# uNimbus_board_1_v1_2.net
KiCad netlist of a schematic drawn in EAGLE
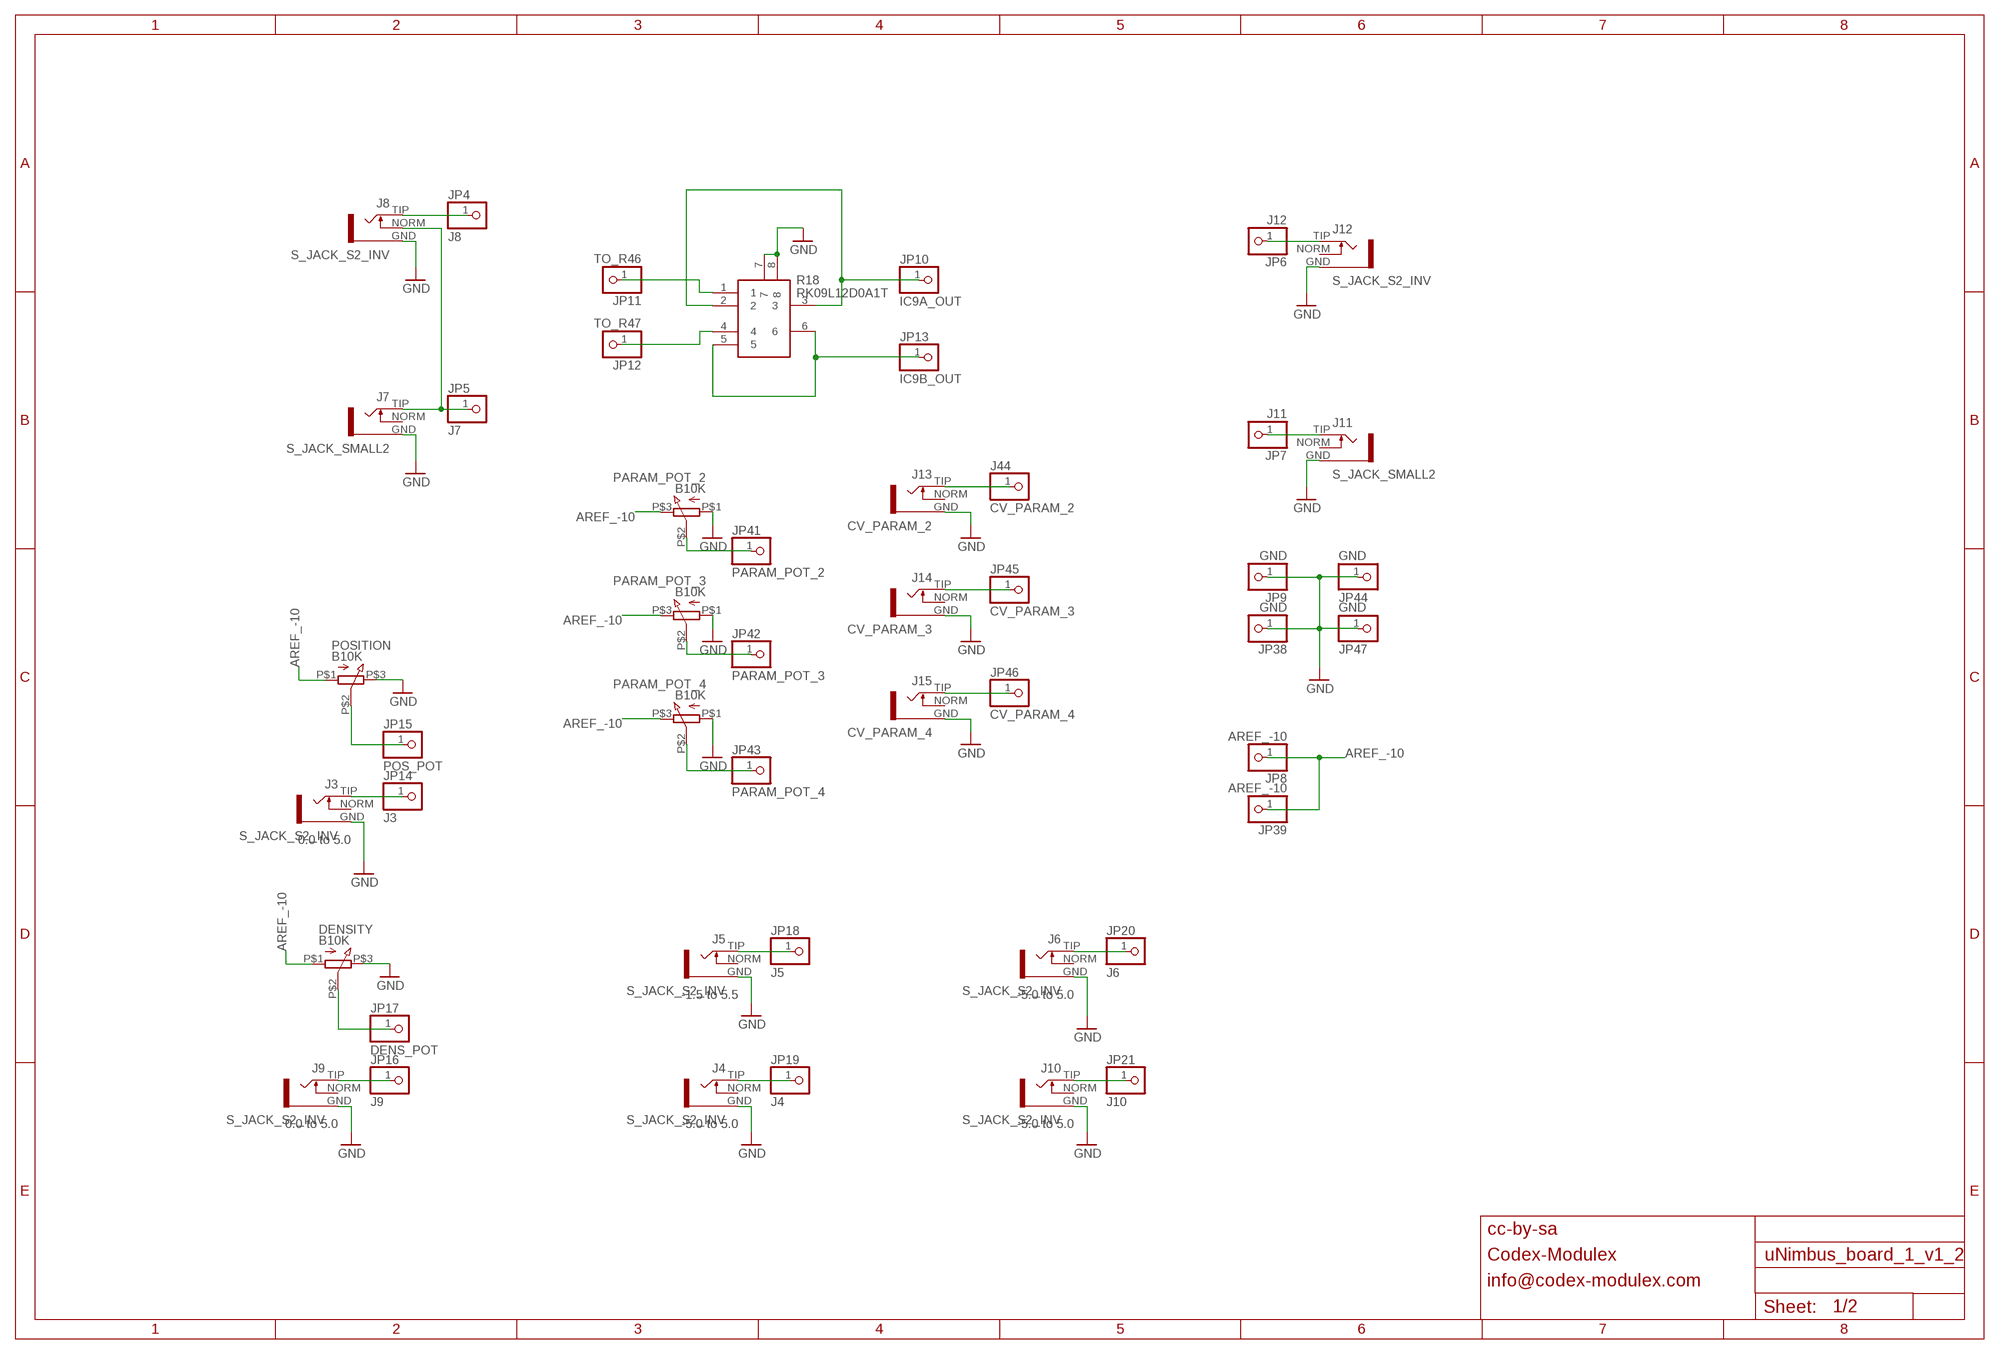
[diagram p0: schematic, sheet 1]
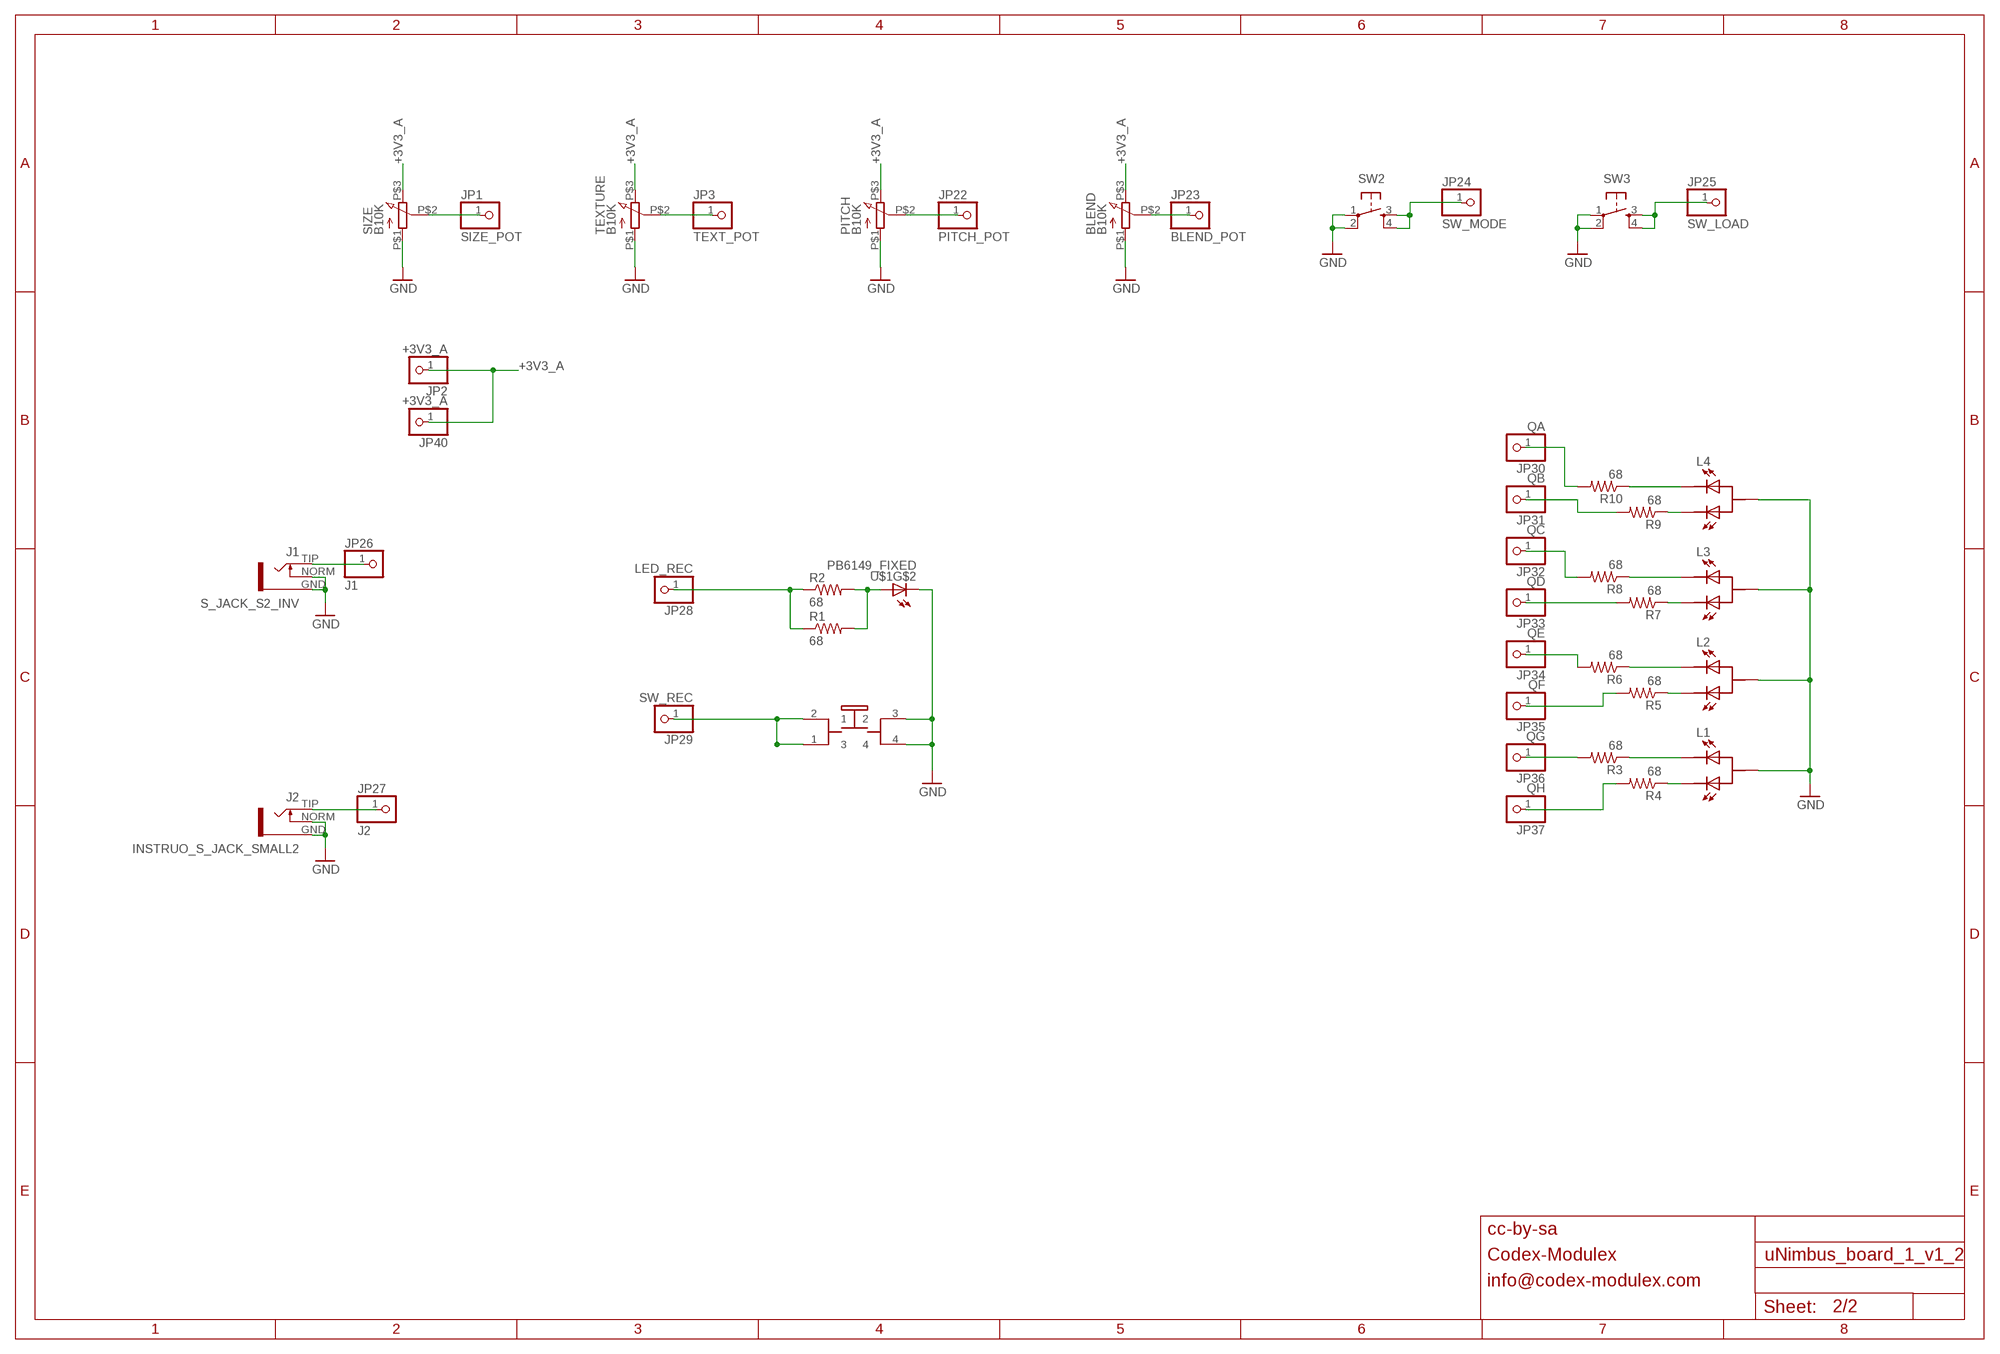
[diagram p1: schematic, sheet 2]

(export (version "E")
  (design (tool "Eeschema 10.0.6"))
  (components
    (comp (ref "BLEND")
      (value "B10K")
      (footprint "eagle-import:Q-POT2")
      (libsource (lib "eagle-import") (part "Q-POT2"))
    )
    (comp (ref "J1")
      (value "S_JACK_S2_INV")
      (footprint "eagle-import:S_JACK_S2_INV")
      (libsource (lib "eagle-import") (part "S_JACK_S2_INV"))
    )
    (comp (ref "J2")
      (value "INSTRUO_S_JACK_SMALL2")
      (footprint "eagle-import:INSTRUO_S_JACK_SMALL2")
      (libsource (lib "eagle-import") (part "INSTRUO_S_JACK_SMALL2"))
    )
    (comp (ref "JP1")
      (value "SIZE_POT")
      (footprint "eagle-import:PARTS_AMAN_1X01")
      (libsource (lib "eagle-import") (part "PARTS_AMAN_PINHD-1X1"))
    )
    (comp (ref "JP2")
      (value "+3V3_A")
      (footprint "eagle-import:PARTS_AMAN_1X01")
      (libsource (lib "eagle-import") (part "PARTS_AMAN_PINHD-1X1"))
    )
    (comp (ref "JP3")
      (value "TEXT_POT")
      (footprint "eagle-import:PARTS_AMAN_1X01")
      (libsource (lib "eagle-import") (part "PARTS_AMAN_PINHD-1X1"))
    )
    (comp (ref "JP22")
      (value "PITCH_POT")
      (footprint "eagle-import:PARTS_AMAN_1X01")
      (libsource (lib "eagle-import") (part "PARTS_AMAN_PINHD-1X1"))
    )
    (comp (ref "JP23")
      (value "BLEND_POT")
      (footprint "eagle-import:PARTS_AMAN_1X01")
      (libsource (lib "eagle-import") (part "PARTS_AMAN_PINHD-1X1"))
    )
    (comp (ref "JP24")
      (value "SW_MODE")
      (footprint "eagle-import:PARTS_AMAN_1X01")
      (libsource (lib "eagle-import") (part "PARTS_AMAN_PINHD-1X1"))
    )
    (comp (ref "JP25")
      (value "SW_LOAD")
      (footprint "eagle-import:PARTS_AMAN_1X01")
      (libsource (lib "eagle-import") (part "PARTS_AMAN_PINHD-1X1"))
    )
    (comp (ref "JP26")
      (value "J1")
      (footprint "eagle-import:PARTS_AMAN_1X01")
      (libsource (lib "eagle-import") (part "PARTS_AMAN_PINHD-1X1"))
    )
    (comp (ref "JP27")
      (value "J2")
      (footprint "eagle-import:PARTS_AMAN_1X01")
      (libsource (lib "eagle-import") (part "PARTS_AMAN_PINHD-1X1"))
    )
    (comp (ref "JP28")
      (value "LED_REC")
      (footprint "eagle-import:PARTS_AMAN_1X01")
      (libsource (lib "eagle-import") (part "PARTS_AMAN_PINHD-1X1"))
    )
    (comp (ref "JP29")
      (value "SW_REC")
      (footprint "eagle-import:PARTS_AMAN_1X01")
      (libsource (lib "eagle-import") (part "PARTS_AMAN_PINHD-1X1"))
    )
    (comp (ref "JP30")
      (value "QA")
      (footprint "eagle-import:PARTS_AMAN_1X01")
      (libsource (lib "eagle-import") (part "PARTS_AMAN_PINHD-1X1"))
    )
    (comp (ref "JP31")
      (value "QB")
      (footprint "eagle-import:PARTS_AMAN_1X01")
      (libsource (lib "eagle-import") (part "PARTS_AMAN_PINHD-1X1"))
    )
    (comp (ref "JP32")
      (value "QC")
      (footprint "eagle-import:PARTS_AMAN_1X01")
      (libsource (lib "eagle-import") (part "PARTS_AMAN_PINHD-1X1"))
    )
    (comp (ref "JP33")
      (value "QD")
      (footprint "eagle-import:PARTS_AMAN_1X01")
      (libsource (lib "eagle-import") (part "PARTS_AMAN_PINHD-1X1"))
    )
    (comp (ref "JP34")
      (value "QE")
      (footprint "eagle-import:PARTS_AMAN_1X01")
      (libsource (lib "eagle-import") (part "PARTS_AMAN_PINHD-1X1"))
    )
    (comp (ref "JP35")
      (value "QF")
      (footprint "eagle-import:PARTS_AMAN_1X01")
      (libsource (lib "eagle-import") (part "PARTS_AMAN_PINHD-1X1"))
    )
    (comp (ref "JP36")
      (value "QG")
      (footprint "eagle-import:PARTS_AMAN_1X01")
      (libsource (lib "eagle-import") (part "PARTS_AMAN_PINHD-1X1"))
    )
    (comp (ref "JP37")
      (value "QH")
      (footprint "eagle-import:PARTS_AMAN_1X01")
      (libsource (lib "eagle-import") (part "PARTS_AMAN_PINHD-1X1"))
    )
    (comp (ref "JP40")
      (value "+3V3_A")
      (footprint "eagle-import:PARTS_AMAN_1X01")
      (libsource (lib "eagle-import") (part "PARTS_AMAN_PINHD-1X1"))
    )
    (comp (ref "L1")
      (value "LED_3MM_3PIN")
      (footprint "eagle-import:LED_3MM_3PIN")
      (libsource (lib "eagle-import") (part "LED_3MM_3PIN"))
    )
    (comp (ref "L2")
      (value "LED_3MM_3PIN")
      (footprint "eagle-import:LED_3MM_3PIN")
      (libsource (lib "eagle-import") (part "LED_3MM_3PIN"))
    )
    (comp (ref "L3")
      (value "LED_3MM_3PIN")
      (footprint "eagle-import:LED_3MM_3PIN")
      (libsource (lib "eagle-import") (part "LED_3MM_3PIN"))
    )
    (comp (ref "L4")
      (value "LED_3MM_3PIN")
      (footprint "eagle-import:LED_3MM_3PIN")
      (libsource (lib "eagle-import") (part "LED_3MM_3PIN"))
    )
    (comp (ref "PITCH")
      (value "B10K")
      (footprint "eagle-import:Q-POT2")
      (libsource (lib "eagle-import") (part "Q-POT2"))
    )
    (comp (ref "R1")
      (value "68")
      (footprint "eagle-import:R0603")
      (libsource (lib "eagle-import") (part "R-US_R0603"))
    )
    (comp (ref "R2")
      (value "68")
      (footprint "eagle-import:R0603")
      (libsource (lib "eagle-import") (part "R-US_R0603"))
    )
    (comp (ref "R3")
      (value "68")
      (footprint "eagle-import:R0603")
      (libsource (lib "eagle-import") (part "R-US_R0603"))
    )
    (comp (ref "R4")
      (value "68")
      (footprint "eagle-import:R0603")
      (libsource (lib "eagle-import") (part "R-US_R0603"))
    )
    (comp (ref "R5")
      (value "68")
      (footprint "eagle-import:R0603")
      (libsource (lib "eagle-import") (part "R-US_R0603"))
    )
    (comp (ref "R6")
      (value "68")
      (footprint "eagle-import:R0603")
      (libsource (lib "eagle-import") (part "R-US_R0603"))
    )
    (comp (ref "R7")
      (value "68")
      (footprint "eagle-import:R0603")
      (libsource (lib "eagle-import") (part "R-US_R0603"))
    )
    (comp (ref "R8")
      (value "68")
      (footprint "eagle-import:R0603")
      (libsource (lib "eagle-import") (part "R-US_R0603"))
    )
    (comp (ref "R9")
      (value "68")
      (footprint "eagle-import:R0603")
      (libsource (lib "eagle-import") (part "R-US_R0603"))
    )
    (comp (ref "R10")
      (value "68")
      (footprint "eagle-import:R0603")
      (libsource (lib "eagle-import") (part "R-US_R0603"))
    )
    (comp (ref "SIZE")
      (value "B10K")
      (footprint "eagle-import:Q-POT2")
      (libsource (lib "eagle-import") (part "Q-POT2"))
    )
    (comp (ref "SW2")
      (value "TAC_SWITCHPTH")
      (footprint "eagle-import:TACTILE-PTH")
      (libsource (lib "eagle-import") (part "TAC_SWITCHPTH"))
    )
    (comp (ref "SW3")
      (value "TAC_SWITCHPTH")
      (footprint "eagle-import:TACTILE-PTH")
      (libsource (lib "eagle-import") (part "TAC_SWITCHPTH"))
    )
    (comp (ref "TEXTURE")
      (value "B10K")
      (footprint "eagle-import:Q-POT2")
      (libsource (lib "eagle-import") (part "Q-POT2"))
    )
    (comp (ref "U$1")
      (value "PB6149_FIXED")
      (footprint "eagle-import:PB6149L")
      (libsource (lib "eagle-import") (part "PB6149_FIXED"))
    )
    (comp (ref "DENSITY")
      (value "B10K")
      (footprint "eagle-import:Q-POT2")
      (libsource (lib "eagle-import") (part "Q-POT2"))
    )
    (comp (ref "J3")
      (value "S_JACK_S2_INV")
      (footprint "eagle-import:S_JACK_S2_INV")
      (libsource (lib "eagle-import") (part "uClouds_002_S_JACK_S2_INV"))
    )
    (comp (ref "J4")
      (value "S_JACK_S2_INV")
      (footprint "eagle-import:S_JACK_S2_INV")
      (libsource (lib "eagle-import") (part "S_JACK_S2_INV"))
    )
    (comp (ref "J5")
      (value "S_JACK_S2_INV")
      (footprint "eagle-import:S_JACK_S2_INV")
      (libsource (lib "eagle-import") (part "S_JACK_S2_INV"))
    )
    (comp (ref "J6")
      (value "S_JACK_S2_INV")
      (footprint "eagle-import:S_JACK_S2_INV")
      (libsource (lib "eagle-import") (part "S_JACK_S2_INV"))
    )
    (comp (ref "J7")
      (value "S_JACK_SMALL2")
      (footprint "eagle-import:S_JACK_SMALL2")
      (libsource (lib "eagle-import") (part "INSTRUO_S_JACK_SMALL2"))
    )
    (comp (ref "J8")
      (value "S_JACK_S2_INV")
      (footprint "eagle-import:S_JACK_S2_INV")
      (libsource (lib "eagle-import") (part "S_JACK_S2_INV"))
    )
    (comp (ref "J9")
      (value "S_JACK_S2_INV")
      (footprint "eagle-import:S_JACK_S2_INV")
      (libsource (lib "eagle-import") (part "S_JACK_S2_INV"))
    )
    (comp (ref "J10")
      (value "S_JACK_S2_INV")
      (footprint "eagle-import:S_JACK_S2_INV")
      (libsource (lib "eagle-import") (part "S_JACK_S2_INV"))
    )
    (comp (ref "J11")
      (value "S_JACK_SMALL2")
      (footprint "eagle-import:S_JACK_SMALL2")
      (libsource (lib "eagle-import") (part "uClouds_002_S_JACK_SMALL2"))
    )
    (comp (ref "J12")
      (value "S_JACK_S2_INV")
      (footprint "eagle-import:S_JACK_S2_INV")
      (libsource (lib "eagle-import") (part "S_JACK_S2_INV"))
    )
    (comp (ref "J13")
      (value "CV_PARAM_2")
      (footprint "eagle-import:S_JACK_S2_INV")
      (libsource (lib "eagle-import") (part "S_JACK_S2_INV"))
    )
    (comp (ref "J14")
      (value "CV_PARAM_3")
      (footprint "eagle-import:S_JACK_S2_INV")
      (libsource (lib "eagle-import") (part "S_JACK_S2_INV"))
    )
    (comp (ref "J15")
      (value "CV_PARAM_4")
      (footprint "eagle-import:S_JACK_S2_INV")
      (libsource (lib "eagle-import") (part "S_JACK_S2_INV"))
    )
    (comp (ref "J44")
      (value "CV_PARAM_2")
      (footprint "eagle-import:PARTS_AMAN_1X01")
      (libsource (lib "eagle-import") (part "PARTS_AMAN_PINHD-1X1"))
    )
    (comp (ref "JP4")
      (value "J8")
      (footprint "eagle-import:PARTS_AMAN_1X01")
      (libsource (lib "eagle-import") (part "PARTS_AMAN_PINHD-1X1"))
    )
    (comp (ref "JP5")
      (value "J7")
      (footprint "eagle-import:PARTS_AMAN_1X01")
      (libsource (lib "eagle-import") (part "PARTS_AMAN_PINHD-1X1"))
    )
    (comp (ref "JP6")
      (value "J12")
      (footprint "eagle-import:PARTS_AMAN_1X01")
      (libsource (lib "eagle-import") (part "PARTS_AMAN_PINHD-1X1"))
    )
    (comp (ref "JP7")
      (value "J11")
      (footprint "eagle-import:PARTS_AMAN_1X01")
      (libsource (lib "eagle-import") (part "PARTS_AMAN_PINHD-1X1"))
    )
    (comp (ref "JP8")
      (value "AREF_-10")
      (footprint "eagle-import:PARTS_AMAN_1X01")
      (libsource (lib "eagle-import") (part "PARTS_AMAN_PINHD-1X1"))
    )
    (comp (ref "JP9")
      (value "GND")
      (footprint "eagle-import:PARTS_AMAN_1X01")
      (libsource (lib "eagle-import") (part "PARTS_AMAN_PINHD-1X1"))
    )
    (comp (ref "JP10")
      (value "IC9A_OUT")
      (footprint "eagle-import:PARTS_AMAN_1X01")
      (libsource (lib "eagle-import") (part "PARTS_AMAN_PINHD-1X1"))
    )
    (comp (ref "JP11")
      (value "TO_R46")
      (footprint "eagle-import:PARTS_AMAN_1X01")
      (libsource (lib "eagle-import") (part "PARTS_AMAN_PINHD-1X1"))
    )
    (comp (ref "JP12")
      (value "TO_R47")
      (footprint "eagle-import:PARTS_AMAN_1X01")
      (libsource (lib "eagle-import") (part "PARTS_AMAN_PINHD-1X1"))
    )
    (comp (ref "JP13")
      (value "IC9B_OUT")
      (footprint "eagle-import:PARTS_AMAN_1X01")
      (libsource (lib "eagle-import") (part "PARTS_AMAN_PINHD-1X1"))
    )
    (comp (ref "JP14")
      (value "J3")
      (footprint "eagle-import:PARTS_AMAN_1X01")
      (libsource (lib "eagle-import") (part "PARTS_AMAN_PINHD-1X1"))
    )
    (comp (ref "JP15")
      (value "POS_POT")
      (footprint "eagle-import:PARTS_AMAN_1X01")
      (libsource (lib "eagle-import") (part "PARTS_AMAN_PINHD-1X1"))
    )
    (comp (ref "JP16")
      (value "J9")
      (footprint "eagle-import:PARTS_AMAN_1X01")
      (libsource (lib "eagle-import") (part "PARTS_AMAN_PINHD-1X1"))
    )
    (comp (ref "JP17")
      (value "DENS_POT")
      (footprint "eagle-import:PARTS_AMAN_1X01")
      (libsource (lib "eagle-import") (part "PARTS_AMAN_PINHD-1X1"))
    )
    (comp (ref "JP18")
      (value "J5")
      (footprint "eagle-import:PARTS_AMAN_1X01")
      (libsource (lib "eagle-import") (part "PARTS_AMAN_PINHD-1X1"))
    )
    (comp (ref "JP19")
      (value "J4")
      (footprint "eagle-import:PARTS_AMAN_1X01")
      (libsource (lib "eagle-import") (part "PARTS_AMAN_PINHD-1X1"))
    )
    (comp (ref "JP20")
      (value "J6")
      (footprint "eagle-import:PARTS_AMAN_1X01")
      (libsource (lib "eagle-import") (part "PARTS_AMAN_PINHD-1X1"))
    )
    (comp (ref "JP21")
      (value "J10")
      (footprint "eagle-import:PARTS_AMAN_1X01")
      (libsource (lib "eagle-import") (part "PARTS_AMAN_PINHD-1X1"))
    )
    (comp (ref "JP38")
      (value "GND")
      (footprint "eagle-import:PARTS_AMAN_1X01")
      (libsource (lib "eagle-import") (part "PARTS_AMAN_PINHD-1X1"))
    )
    (comp (ref "JP39")
      (value "AREF_-10")
      (footprint "eagle-import:PARTS_AMAN_1X01")
      (libsource (lib "eagle-import") (part "PARTS_AMAN_PINHD-1X1"))
    )
    (comp (ref "JP41")
      (value "PARAM_POT_2")
      (footprint "eagle-import:PARTS_AMAN_1X01")
      (libsource (lib "eagle-import") (part "PARTS_AMAN_PINHD-1X1"))
    )
    (comp (ref "JP42")
      (value "PARAM_POT_3")
      (footprint "eagle-import:PARTS_AMAN_1X01")
      (libsource (lib "eagle-import") (part "PARTS_AMAN_PINHD-1X1"))
    )
    (comp (ref "JP43")
      (value "PARAM_POT_4")
      (footprint "eagle-import:PARTS_AMAN_1X01")
      (libsource (lib "eagle-import") (part "PARTS_AMAN_PINHD-1X1"))
    )
    (comp (ref "JP44")
      (value "GND")
      (footprint "eagle-import:PARTS_AMAN_1X01")
      (libsource (lib "eagle-import") (part "PARTS_AMAN_PINHD-1X1"))
    )
    (comp (ref "JP45")
      (value "CV_PARAM_3")
      (footprint "eagle-import:PARTS_AMAN_1X01")
      (libsource (lib "eagle-import") (part "PARTS_AMAN_PINHD-1X1"))
    )
    (comp (ref "JP46")
      (value "CV_PARAM_4")
      (footprint "eagle-import:PARTS_AMAN_1X01")
      (libsource (lib "eagle-import") (part "PARTS_AMAN_PINHD-1X1"))
    )
    (comp (ref "JP47")
      (value "GND")
      (footprint "eagle-import:PARTS_AMAN_1X01")
      (libsource (lib "eagle-import") (part "PARTS_AMAN_PINHD-1X1"))
    )
    (comp (ref "PARAM_POT_2")
      (value "B10K")
      (footprint "eagle-import:Q-POT2")
      (libsource (lib "eagle-import") (part "uClouds_002_Q-POT2"))
    )
    (comp (ref "PARAM_POT_3")
      (value "B10K")
      (footprint "eagle-import:Q-POT2")
      (libsource (lib "eagle-import") (part "uClouds_002_Q-POT2"))
    )
    (comp (ref "PARAM_POT_4")
      (value "B10K")
      (footprint "eagle-import:Q-POT2")
      (libsource (lib "eagle-import") (part "uClouds_002_Q-POT2"))
    )
    (comp (ref "POSITION")
      (value "B10K")
      (footprint "eagle-import:Q-POT2")
      (libsource (lib "eagle-import") (part "Q-POT2"))
    )
    (comp (ref "R18")
      (value "RK09L12D0A1T")
      (footprint "eagle-import:RK09L12D0A1T")
      (fields (field (name "MOUSER_PART_NUMBER") "688-RK09L12D0A1T"))
      (libsource (lib "eagle-import") (part "RK09L12D0A1T"))
    )
  )
  (nets
    (net (code "1") (name "+3V3_A") (class "Default")
      (node (ref "BLEND") (pin "P$3") (pinfunction "3_P$3") (pintype "passive"))
      (node (ref "JP2") (pin "1") (pinfunction "1_1") (pintype "passive"))
      (node (ref "JP40") (pin "1") (pinfunction "1_1") (pintype "passive"))
      (node (ref "PITCH") (pin "P$3") (pinfunction "3_P$3") (pintype "passive"))
      (node (ref "SIZE") (pin "P$3") (pinfunction "3_P$3") (pintype "passive"))
      (node (ref "TEXTURE") (pin "P$3") (pinfunction "3_P$3") (pintype "passive"))
    )
    (net (code "2") (name "AREF_-10") (class "Default")
      (node (ref "DENSITY") (pin "P$1") (pinfunction "1_P$1") (pintype "passive"))
      (node (ref "JP39") (pin "1") (pinfunction "1_1") (pintype "passive"))
      (node (ref "JP8") (pin "1") (pinfunction "1_1") (pintype "passive"))
      (node (ref "PARAM_POT_2") (pin "P$3") (pinfunction "3_P$3") (pintype "passive"))
      (node (ref "PARAM_POT_3") (pin "P$3") (pinfunction "3_P$3") (pintype "passive"))
      (node (ref "PARAM_POT_4") (pin "P$3") (pinfunction "3_P$3") (pintype "passive"))
      (node (ref "POSITION") (pin "P$1") (pinfunction "1_P$1") (pintype "passive"))
    )
    (net (code "3") (name "GND") (class "Default")
      (node (ref "BLEND") (pin "P$1") (pinfunction "1_P$1") (pintype "passive"))
      (node (ref "DENSITY") (pin "P$3") (pinfunction "3_P$3") (pintype "passive"))
      (node (ref "J1") (pin "GND") (pinfunction "GND_GND") (pintype "passive"))
      (node (ref "J1") (pin "NORM") (pinfunction "NORM_NORM") (pintype "passive"))
      (node (ref "J10") (pin "GND") (pinfunction "GND_GND") (pintype "passive"))
      (node (ref "J11") (pin "GND") (pinfunction "GND_GND") (pintype "passive"))
      (node (ref "J12") (pin "GND") (pinfunction "GND_GND") (pintype "passive"))
      (node (ref "J13") (pin "GND") (pinfunction "GND_GND") (pintype "passive"))
      (node (ref "J14") (pin "GND") (pinfunction "GND_GND") (pintype "passive"))
      (node (ref "J15") (pin "GND") (pinfunction "GND_GND") (pintype "passive"))
      (node (ref "J2") (pin "GND") (pinfunction "GND_GND") (pintype "passive"))
      (node (ref "J2") (pin "NORM") (pinfunction "NORM_NORM") (pintype "passive"))
      (node (ref "J3") (pin "GND") (pinfunction "GND_GND") (pintype "passive"))
      (node (ref "J4") (pin "GND") (pinfunction "GND_GND") (pintype "passive"))
      (node (ref "J5") (pin "GND") (pinfunction "GND_GND") (pintype "passive"))
      (node (ref "J6") (pin "GND") (pinfunction "GND_GND") (pintype "passive"))
      (node (ref "J7") (pin "GND") (pinfunction "GND_GND") (pintype "passive"))
      (node (ref "J8") (pin "GND") (pinfunction "GND_GND") (pintype "passive"))
      (node (ref "J9") (pin "GND") (pinfunction "GND_GND") (pintype "passive"))
      (node (ref "JP38") (pin "1") (pinfunction "1_1") (pintype "passive"))
      (node (ref "JP44") (pin "1") (pinfunction "1_1") (pintype "passive"))
      (node (ref "JP47") (pin "1") (pinfunction "1_1") (pintype "passive"))
      (node (ref "JP9") (pin "1") (pinfunction "1_1") (pintype "passive"))
      (node (ref "L1") (pin "A") (pinfunction "A_A") (pintype "passive"))
      (node (ref "L2") (pin "A") (pinfunction "A_A") (pintype "passive"))
      (node (ref "L3") (pin "A") (pinfunction "A_A") (pintype "passive"))
      (node (ref "L4") (pin "A") (pinfunction "A_A") (pintype "passive"))
      (node (ref "PARAM_POT_2") (pin "P$1") (pinfunction "1_P$1") (pintype "passive"))
      (node (ref "PARAM_POT_3") (pin "P$1") (pinfunction "1_P$1") (pintype "passive"))
      (node (ref "PARAM_POT_4") (pin "P$1") (pinfunction "1_P$1") (pintype "passive"))
      (node (ref "PITCH") (pin "P$1") (pinfunction "1_P$1") (pintype "passive"))
      (node (ref "POSITION") (pin "P$3") (pinfunction "3_P$3") (pintype "passive"))
      (node (ref "R18") (pin "7") (pinfunction "7_7") (pintype "bidirectional"))
      (node (ref "R18") (pin "8") (pinfunction "8_8") (pintype "bidirectional"))
      (node (ref "SIZE") (pin "P$1") (pinfunction "1_P$1") (pintype "passive"))
      (node (ref "SW2") (pin "1") (pinfunction "1_1") (pintype "passive"))
      (node (ref "SW2") (pin "2") (pinfunction "2_2") (pintype "passive"))
      (node (ref "SW3") (pin "1") (pinfunction "1_1") (pintype "passive"))
      (node (ref "SW3") (pin "2") (pinfunction "2_2") (pintype "passive"))
      (node (ref "TEXTURE") (pin "P$1") (pinfunction "1_P$1") (pintype "passive"))
      (node (ref "U$1") (pin "3") (pinfunction "2_3") (pintype "bidirectional"))
      (node (ref "U$1") (pin "4") (pinfunction "4_4") (pintype "bidirectional"))
      (node (ref "U$1") (pin "K") (pinfunction "C_K") (pintype "passive"))
    )
    (net (code "4") (name "Net-(BLEND-2)") (class "Default")
      (node (ref "BLEND") (pin "P$2") (pinfunction "2_P$2") (pintype "passive"))
      (node (ref "JP23") (pin "1") (pinfunction "1_1") (pintype "passive"))
    )
    (net (code "5") (name "Net-(DENSITY-2)") (class "Default")
      (node (ref "DENSITY") (pin "P$2") (pinfunction "2_P$2") (pintype "passive"))
      (node (ref "JP17") (pin "1") (pinfunction "1_1") (pintype "passive"))
    )
    (net (code "6") (name "Net-(J1-PadTIP)") (class "Default")
      (node (ref "J1") (pin "TIP") (pinfunction "TIP_TIP") (pintype "passive"))
      (node (ref "JP26") (pin "1") (pinfunction "1_1") (pintype "passive"))
    )
    (net (code "7") (name "Net-(J2-PadTIP)") (class "Default")
      (node (ref "J2") (pin "TIP") (pinfunction "TIP_TIP") (pintype "passive"))
      (node (ref "JP27") (pin "1") (pinfunction "1_1") (pintype "passive"))
    )
    (net (code "8") (name "Net-(J3-PadTIP)") (class "Default")
      (node (ref "J3") (pin "TIP") (pinfunction "TIP_TIP") (pintype "passive"))
      (node (ref "JP14") (pin "1") (pinfunction "1_1") (pintype "passive"))
    )
    (net (code "9") (name "Net-(J4-PadTIP)") (class "Default")
      (node (ref "J4") (pin "TIP") (pinfunction "TIP_TIP") (pintype "passive"))
      (node (ref "JP19") (pin "1") (pinfunction "1_1") (pintype "passive"))
    )
    (net (code "10") (name "Net-(J5-PadTIP)") (class "Default")
      (node (ref "J5") (pin "TIP") (pinfunction "TIP_TIP") (pintype "passive"))
      (node (ref "JP18") (pin "1") (pinfunction "1_1") (pintype "passive"))
    )
    (net (code "11") (name "Net-(J6-PadTIP)") (class "Default")
      (node (ref "J6") (pin "TIP") (pinfunction "TIP_TIP") (pintype "passive"))
      (node (ref "JP20") (pin "1") (pinfunction "1_1") (pintype "passive"))
    )
    (net (code "12") (name "Net-(J7-PadTIP)") (class "Default")
      (node (ref "J7") (pin "TIP") (pinfunction "TIP_TIP") (pintype "passive"))
      (node (ref "J8") (pin "NORM") (pinfunction "NORM_NORM") (pintype "passive"))
      (node (ref "JP5") (pin "1") (pinfunction "1_1") (pintype "passive"))
    )
    (net (code "13") (name "Net-(J8-PadTIP)") (class "Default")
      (node (ref "J8") (pin "TIP") (pinfunction "TIP_TIP") (pintype "passive"))
      (node (ref "JP4") (pin "1") (pinfunction "1_1") (pintype "passive"))
    )
    (net (code "14") (name "Net-(J9-PadTIP)") (class "Default")
      (node (ref "J9") (pin "TIP") (pinfunction "TIP_TIP") (pintype "passive"))
      (node (ref "JP16") (pin "1") (pinfunction "1_1") (pintype "passive"))
    )
    (net (code "15") (name "Net-(J10-PadTIP)") (class "Default")
      (node (ref "J10") (pin "TIP") (pinfunction "TIP_TIP") (pintype "passive"))
      (node (ref "JP21") (pin "1") (pinfunction "1_1") (pintype "passive"))
    )
    (net (code "16") (name "Net-(J11-PadTIP)") (class "Default")
      (node (ref "J11") (pin "TIP") (pinfunction "TIP_TIP") (pintype "passive"))
      (node (ref "JP7") (pin "1") (pinfunction "1_1") (pintype "passive"))
    )
    (net (code "17") (name "Net-(J12-PadTIP)") (class "Default")
      (node (ref "J12") (pin "TIP") (pinfunction "TIP_TIP") (pintype "passive"))
      (node (ref "JP6") (pin "1") (pinfunction "1_1") (pintype "passive"))
    )
    (net (code "18") (name "Net-(J13-PadTIP)") (class "Default")
      (node (ref "J13") (pin "TIP") (pinfunction "TIP_TIP") (pintype "passive"))
      (node (ref "J44") (pin "1") (pinfunction "1_1") (pintype "passive"))
    )
    (net (code "19") (name "Net-(J14-PadTIP)") (class "Default")
      (node (ref "J14") (pin "TIP") (pinfunction "TIP_TIP") (pintype "passive"))
      (node (ref "JP45") (pin "1") (pinfunction "1_1") (pintype "passive"))
    )
    (net (code "20") (name "Net-(J15-PadTIP)") (class "Default")
      (node (ref "J15") (pin "TIP") (pinfunction "TIP_TIP") (pintype "passive"))
      (node (ref "JP46") (pin "1") (pinfunction "1_1") (pintype "passive"))
    )
    (net (code "21") (name "Net-(JP10-Pad1)") (class "Default")
      (node (ref "JP10") (pin "1") (pinfunction "1_1") (pintype "passive"))
      (node (ref "R18") (pin "2") (pinfunction "2_2") (pintype "bidirectional"))
      (node (ref "R18") (pin "3") (pinfunction "3_3") (pintype "bidirectional"))
    )
    (net (code "22") (name "Net-(JP11-Pad1)") (class "Default")
      (node (ref "JP11") (pin "1") (pinfunction "1_1") (pintype "passive"))
      (node (ref "R18") (pin "1") (pinfunction "1_1") (pintype "bidirectional"))
    )
    (net (code "23") (name "Net-(JP12-Pad1)") (class "Default")
      (node (ref "JP12") (pin "1") (pinfunction "1_1") (pintype "passive"))
      (node (ref "R18") (pin "4") (pinfunction "4_4") (pintype "bidirectional"))
    )
    (net (code "24") (name "Net-(JP13-Pad1)") (class "Default")
      (node (ref "JP13") (pin "1") (pinfunction "1_1") (pintype "passive"))
      (node (ref "R18") (pin "5") (pinfunction "5_5") (pintype "bidirectional"))
      (node (ref "R18") (pin "6") (pinfunction "6_6") (pintype "bidirectional"))
    )
    (net (code "25") (name "Net-(JP24-Pad1)") (class "Default")
      (node (ref "JP24") (pin "1") (pinfunction "1_1") (pintype "passive"))
      (node (ref "SW2") (pin "3") (pinfunction "3_3") (pintype "passive"))
      (node (ref "SW2") (pin "4") (pinfunction "4_4") (pintype "passive"))
    )
    (net (code "26") (name "Net-(JP25-Pad1)") (class "Default")
      (node (ref "JP25") (pin "1") (pinfunction "1_1") (pintype "passive"))
      (node (ref "SW3") (pin "3") (pinfunction "3_3") (pintype "passive"))
      (node (ref "SW3") (pin "4") (pinfunction "4_4") (pintype "passive"))
    )
    (net (code "27") (name "Net-(JP28-Pad1)") (class "Default")
      (node (ref "JP28") (pin "1") (pinfunction "1_1") (pintype "passive"))
      (node (ref "R1") (pin "1") (pinfunction "1_1") (pintype "passive"))
      (node (ref "R2") (pin "1") (pinfunction "1_1") (pintype "passive"))
    )
    (net (code "28") (name "Net-(JP30-Pad1)") (class "Default")
      (node (ref "JP30") (pin "1") (pinfunction "1_1") (pintype "passive"))
      (node (ref "R10") (pin "2") (pinfunction "2_2") (pintype "passive"))
    )
    (net (code "29") (name "Net-(JP31-Pad1)") (class "Default")
      (node (ref "JP31") (pin "1") (pinfunction "1_1") (pintype "passive"))
      (node (ref "R9") (pin "2") (pinfunction "2_2") (pintype "passive"))
    )
    (net (code "30") (name "Net-(JP32-Pad1)") (class "Default")
      (node (ref "JP32") (pin "1") (pinfunction "1_1") (pintype "passive"))
      (node (ref "R8") (pin "2") (pinfunction "2_2") (pintype "passive"))
    )
    (net (code "31") (name "Net-(JP33-Pad1)") (class "Default")
      (node (ref "JP33") (pin "1") (pinfunction "1_1") (pintype "passive"))
      (node (ref "R7") (pin "2") (pinfunction "2_2") (pintype "passive"))
    )
    (net (code "32") (name "Net-(JP34-Pad1)") (class "Default")
      (node (ref "JP34") (pin "1") (pinfunction "1_1") (pintype "passive"))
      (node (ref "R6") (pin "2") (pinfunction "2_2") (pintype "passive"))
    )
    (net (code "33") (name "Net-(JP35-Pad1)") (class "Default")
      (node (ref "JP35") (pin "1") (pinfunction "1_1") (pintype "passive"))
      (node (ref "R5") (pin "2") (pinfunction "2_2") (pintype "passive"))
    )
    (net (code "34") (name "Net-(JP36-Pad1)") (class "Default")
      (node (ref "JP36") (pin "1") (pinfunction "1_1") (pintype "passive"))
      (node (ref "R3") (pin "2") (pinfunction "2_2") (pintype "passive"))
    )
    (net (code "35") (name "Net-(JP37-Pad1)") (class "Default")
      (node (ref "JP37") (pin "1") (pinfunction "1_1") (pintype "passive"))
      (node (ref "R4") (pin "2") (pinfunction "2_2") (pintype "passive"))
    )
    (net (code "36") (name "Net-(L1-PadC1)") (class "Default")
      (node (ref "L1") (pin "C1") (pinfunction "C1_C1") (pintype "passive"))
      (node (ref "R4") (pin "1") (pinfunction "1_1") (pintype "passive"))
    )
    (net (code "37") (name "Net-(L1-PadC2)") (class "Default")
      (node (ref "L1") (pin "C2") (pinfunction "C2_C2") (pintype "passive"))
      (node (ref "R3") (pin "1") (pinfunction "1_1") (pintype "passive"))
    )
    (net (code "38") (name "Net-(L2-PadC1)") (class "Default")
      (node (ref "L2") (pin "C1") (pinfunction "C1_C1") (pintype "passive"))
      (node (ref "R5") (pin "1") (pinfunction "1_1") (pintype "passive"))
    )
    (net (code "39") (name "Net-(L2-PadC2)") (class "Default")
      (node (ref "L2") (pin "C2") (pinfunction "C2_C2") (pintype "passive"))
      (node (ref "R6") (pin "1") (pinfunction "1_1") (pintype "passive"))
    )
    (net (code "40") (name "Net-(L3-PadC1)") (class "Default")
      (node (ref "L3") (pin "C1") (pinfunction "C1_C1") (pintype "passive"))
      (node (ref "R7") (pin "1") (pinfunction "1_1") (pintype "passive"))
    )
    (net (code "41") (name "Net-(L3-PadC2)") (class "Default")
      (node (ref "L3") (pin "C2") (pinfunction "C2_C2") (pintype "passive"))
      (node (ref "R8") (pin "1") (pinfunction "1_1") (pintype "passive"))
    )
    (net (code "42") (name "Net-(L4-PadC1)") (class "Default")
      (node (ref "L4") (pin "C1") (pinfunction "C1_C1") (pintype "passive"))
      (node (ref "R9") (pin "1") (pinfunction "1_1") (pintype "passive"))
    )
    (net (code "43") (name "Net-(L4-PadC2)") (class "Default")
      (node (ref "L4") (pin "C2") (pinfunction "C2_C2") (pintype "passive"))
      (node (ref "R10") (pin "1") (pinfunction "1_1") (pintype "passive"))
    )
    (net (code "44") (name "Net-(PARAM_POT_2-2)") (class "Default")
      (node (ref "JP41") (pin "1") (pinfunction "1_1") (pintype "passive"))
      (node (ref "PARAM_POT_2") (pin "P$2") (pinfunction "2_P$2") (pintype "passive"))
    )
    (net (code "45") (name "Net-(PARAM_POT_3-2)") (class "Default")
      (node (ref "JP42") (pin "1") (pinfunction "1_1") (pintype "passive"))
      (node (ref "PARAM_POT_3") (pin "P$2") (pinfunction "2_P$2") (pintype "passive"))
    )
    (net (code "46") (name "Net-(PARAM_POT_4-2)") (class "Default")
      (node (ref "JP43") (pin "1") (pinfunction "1_1") (pintype "passive"))
      (node (ref "PARAM_POT_4") (pin "P$2") (pinfunction "2_P$2") (pintype "passive"))
    )
    (net (code "47") (name "Net-(PITCH-2)") (class "Default")
      (node (ref "JP22") (pin "1") (pinfunction "1_1") (pintype "passive"))
      (node (ref "PITCH") (pin "P$2") (pinfunction "2_P$2") (pintype "passive"))
    )
    (net (code "48") (name "Net-(POSITION-2)") (class "Default")
      (node (ref "JP15") (pin "1") (pinfunction "1_1") (pintype "passive"))
      (node (ref "POSITION") (pin "P$2") (pinfunction "2_P$2") (pintype "passive"))
    )
    (net (code "49") (name "Net-(R1-Pad2)") (class "Default")
      (node (ref "R1") (pin "2") (pinfunction "2_2") (pintype "passive"))
      (node (ref "R2") (pin "2") (pinfunction "2_2") (pintype "passive"))
      (node (ref "U$1") (pin "A") (pinfunction "A_A") (pintype "passive"))
    )
    (net (code "50") (name "Net-(SIZE-2)") (class "Default")
      (node (ref "JP1") (pin "1") (pinfunction "1_1") (pintype "passive"))
      (node (ref "SIZE") (pin "P$2") (pinfunction "2_P$2") (pintype "passive"))
    )
    (net (code "51") (name "Net-(TEXTURE-2)") (class "Default")
      (node (ref "JP3") (pin "1") (pinfunction "1_1") (pintype "passive"))
      (node (ref "TEXTURE") (pin "P$2") (pinfunction "2_P$2") (pintype "passive"))
    )
    (net (code "52") (name "Net-(U$1A-1)") (class "Default")
      (node (ref "JP29") (pin "1") (pinfunction "1_1") (pintype "passive"))
      (node (ref "U$1") (pin "1") (pinfunction "3_1") (pintype "bidirectional"))
      (node (ref "U$1") (pin "2") (pinfunction "1_2") (pintype "bidirectional"))
    )
    (net (code "53") (name "unconnected-(J3-PadNORM)") (class "Default")
      (node (ref "J3") (pin "NORM") (pinfunction "NORM_NORM") (pintype "passive"))
    )
    (net (code "54") (name "unconnected-(J4-PadNORM)") (class "Default")
      (node (ref "J4") (pin "NORM") (pinfunction "NORM_NORM") (pintype "passive"))
    )
    (net (code "55") (name "unconnected-(J5-PadNORM)") (class "Default")
      (node (ref "J5") (pin "NORM") (pinfunction "NORM_NORM") (pintype "passive"))
    )
    (net (code "56") (name "unconnected-(J6-PadNORM)") (class "Default")
      (node (ref "J6") (pin "NORM") (pinfunction "NORM_NORM") (pintype "passive"))
    )
    (net (code "57") (name "unconnected-(J7-PadNORM)") (class "Default")
      (node (ref "J7") (pin "NORM") (pinfunction "NORM_NORM") (pintype "passive"))
    )
    (net (code "58") (name "unconnected-(J9-PadNORM)") (class "Default")
      (node (ref "J9") (pin "NORM") (pinfunction "NORM_NORM") (pintype "passive"))
    )
    (net (code "59") (name "unconnected-(J10-PadNORM)") (class "Default")
      (node (ref "J10") (pin "NORM") (pinfunction "NORM_NORM") (pintype "passive"))
    )
    (net (code "60") (name "unconnected-(J11-PadNORM)") (class "Default")
      (node (ref "J11") (pin "NORM") (pinfunction "NORM_NORM") (pintype "passive"))
    )
    (net (code "61") (name "unconnected-(J12-PadNORM)") (class "Default")
      (node (ref "J12") (pin "NORM") (pinfunction "NORM_NORM") (pintype "passive"))
    )
    (net (code "62") (name "unconnected-(J13-PadNORM)") (class "Default")
      (node (ref "J13") (pin "NORM") (pinfunction "NORM_NORM") (pintype "passive"))
    )
    (net (code "63") (name "unconnected-(J14-PadNORM)") (class "Default")
      (node (ref "J14") (pin "NORM") (pinfunction "NORM_NORM") (pintype "passive"))
    )
    (net (code "64") (name "unconnected-(J15-PadNORM)") (class "Default")
      (node (ref "J15") (pin "NORM") (pinfunction "NORM_NORM") (pintype "passive"))
    )
  )
)
